# Mako_DSP_Power_R1_1.net
KiCad netlist of a schematic drawn in Altium Designer
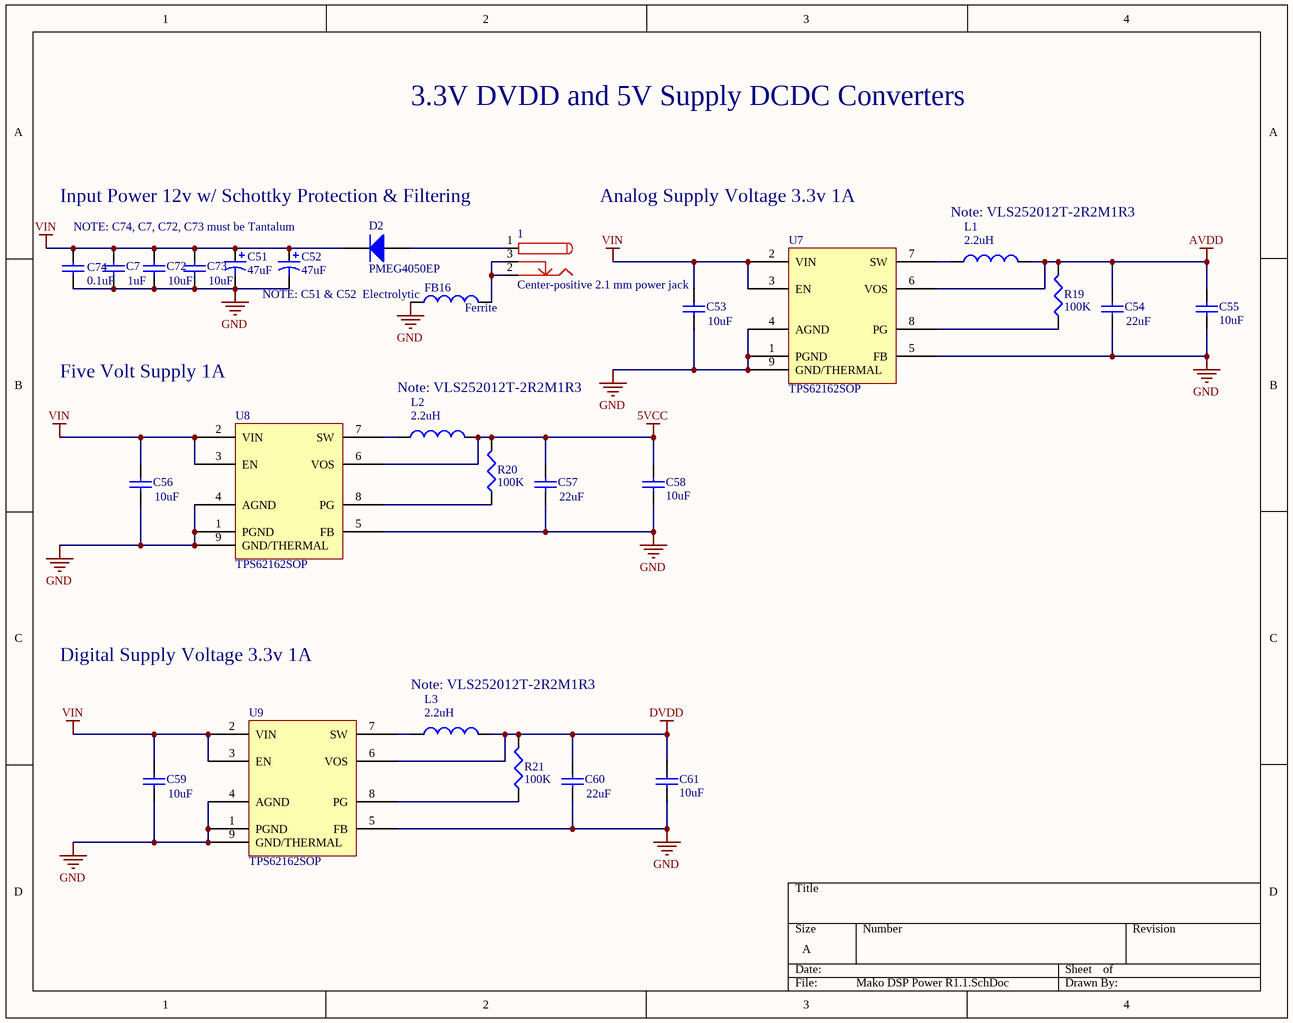
[diagram p0: Mako DSP Power R1.1.SchDoc]

(export (version "E")
  (design (tool "Eeschema 10.0.6"))
  (components
    (comp (ref "1")
      (value "Center-positive 2.1 mm power jack")
      (footprint "PJ-102AH")
      (description "Power jack")
      (fields (field (name "PUBLISHER") "Altium Limited"))
      (libsource (lib "Rascal") (part "PWR2.5"))
    )
    (comp (ref "C7")
      (value "1uF")
      (footprint "C1206")
      (description "Capacitor (Semiconductor SIM Model)")
      (fields (field (name "Comment") "Cap Semi") (field (name "PUBLISHER") "Altium Limited"))
      (libsource (lib "Miscellaneous Devices") (part "Cap Semi"))
    )
    (comp (ref "C51")
      (value "47uF")
      (footprint "CAPPR2.5-6.3x5")
      (description "Polarized Capacitor (Radial)")
      (fields (field (name "Comment") "Cap Pol1") (field (name "PUBLISHER") "Altium Limited"))
      (libsource (lib "Miscellaneous Devices") (part "Cap Pol1"))
    )
    (comp (ref "C52")
      (value "47uF")
      (footprint "CAPPR2.5-6.3x5")
      (description "Polarized Capacitor (Radial)")
      (fields (field (name "Comment") "Cap Pol1") (field (name "PUBLISHER") "Altium Limited"))
      (libsource (lib "Miscellaneous Devices") (part "Cap Pol1"))
    )
    (comp (ref "C53")
      (value "10uF")
      (footprint "C1206")
      (description "Capacitor (Semiconductor SIM Model)")
      (fields (field (name "Comment") "Cap Semi") (field (name "PUBLISHER") "Altium Limited"))
      (libsource (lib "Miscellaneous Devices") (part "Cap Semi"))
    )
    (comp (ref "C54")
      (value "22uF")
      (footprint "C1206")
      (description "Capacitor (Semiconductor SIM Model)")
      (fields (field (name "Comment") "Cap Semi") (field (name "PUBLISHER") "Altium Limited"))
      (libsource (lib "Miscellaneous Devices") (part "Cap Semi"))
    )
    (comp (ref "C55")
      (value "10uF")
      (footprint "Panasonic VS B")
      (description "Capacitor (Semiconductor SIM Model)")
      (fields (field (name "Comment") "Cap Semi") (field (name "PUBLISHER") "Altium Limited"))
      (libsource (lib "Miscellaneous Devices") (part "Cap Semi"))
    )
    (comp (ref "C56")
      (value "10uF")
      (footprint "C1206")
      (description "Capacitor (Semiconductor SIM Model)")
      (fields (field (name "Comment") "Cap Semi") (field (name "PUBLISHER") "Altium Limited"))
      (libsource (lib "Miscellaneous Devices") (part "Cap Semi"))
    )
    (comp (ref "C57")
      (value "22uF")
      (footprint "C1206")
      (description "Capacitor (Semiconductor SIM Model)")
      (fields (field (name "Comment") "Cap Semi") (field (name "PUBLISHER") "Altium Limited"))
      (libsource (lib "Miscellaneous Devices") (part "Cap Semi"))
    )
    (comp (ref "C58")
      (value "10uF")
      (footprint "Panasonic VS B")
      (description "Capacitor (Semiconductor SIM Model)")
      (fields (field (name "Comment") "Cap Semi") (field (name "PUBLISHER") "Altium Limited"))
      (libsource (lib "Miscellaneous Devices") (part "Cap Semi"))
    )
    (comp (ref "C59")
      (value "10uF")
      (footprint "C1206")
      (description "Capacitor (Semiconductor SIM Model)")
      (fields (field (name "Comment") "Cap Semi") (field (name "PUBLISHER") "Altium Limited"))
      (libsource (lib "Miscellaneous Devices") (part "Cap Semi"))
    )
    (comp (ref "C60")
      (value "22uF")
      (footprint "C1206")
      (description "Capacitor (Semiconductor SIM Model)")
      (fields (field (name "Comment") "Cap Semi") (field (name "PUBLISHER") "Altium Limited"))
      (libsource (lib "Miscellaneous Devices") (part "Cap Semi"))
    )
    (comp (ref "C61")
      (value "10uF")
      (footprint "Panasonic VS B")
      (description "Capacitor (Semiconductor SIM Model)")
      (fields (field (name "Comment") "Cap Semi") (field (name "PUBLISHER") "Altium Limited"))
      (libsource (lib "Miscellaneous Devices") (part "Cap Semi"))
    )
    (comp (ref "C72")
      (value "10uF")
      (footprint "C1206")
      (description "Capacitor (Semiconductor SIM Model)")
      (fields (field (name "Comment") "Cap Semi") (field (name "PUBLISHER") "Altium Limited"))
      (libsource (lib "Miscellaneous Devices") (part "Cap Semi"))
    )
    (comp (ref "C73")
      (value "10uF")
      (footprint "C1206")
      (description "Capacitor (Semiconductor SIM Model)")
      (fields (field (name "Comment") "Cap Semi") (field (name "PUBLISHER") "Altium Limited"))
      (libsource (lib "Miscellaneous Devices") (part "Cap Semi"))
    )
    (comp (ref "C74")
      (value "0.1uF")
      (footprint "C1206")
      (description "Capacitor (Semiconductor SIM Model)")
      (fields (field (name "Comment") "Cap Semi") (field (name "PUBLISHER") "Altium Limited"))
      (libsource (lib "Miscellaneous Devices") (part "Cap Semi"))
    )
    (comp (ref "D2")
      (value "PMEG4050EP")
      (footprint "PMEG4050EP")
      (description "Default Diode")
      (fields (field (name "PUBLISHER") "Altium Limited"))
      (libsource (lib "Miscellaneous Devices") (part "Diode"))
    )
    (comp (ref "FB16")
      (value "Ferrite")
      (footprint "SM 0805 - gap trimmed")
      (description "Inductor")
      (fields (field (name "PUBLISHER") "Altium Limited"))
      (libsource (lib "Miscellaneous Devices") (part "Inductor"))
    )
    (comp (ref "L1")
      (value "2.2uH")
      (footprint "VLS252012T-2R2M1R3")
      (description "Inductor")
      (fields (field (name "PUBLISHER") "Altium Limited"))
      (libsource (lib "Miscellaneous Devices") (part "Inductor"))
    )
    (comp (ref "L2")
      (value "2.2uH")
      (footprint "VLS252012T-2R2M1R3")
      (description "Inductor")
      (fields (field (name "PUBLISHER") "Altium Limited"))
      (libsource (lib "Miscellaneous Devices") (part "Inductor"))
    )
    (comp (ref "L3")
      (value "2.2uH")
      (footprint "VLS252012T-2R2M1R3")
      (description "Inductor")
      (fields (field (name "PUBLISHER") "Altium Limited"))
      (libsource (lib "Miscellaneous Devices") (part "Inductor"))
    )
    (comp (ref "R19")
      (value "100K")
      (footprint "RESC2012L")
      (description "Resistor")
      (fields (field (name "Comment") "Res3") (field (name "PUBLISHER") "Altium Limited"))
      (libsource (lib "Miscellaneous Devices") (part "Res3"))
    )
    (comp (ref "R20")
      (value "100K")
      (footprint "RESC2012L")
      (description "Resistor")
      (fields (field (name "Comment") "Res3") (field (name "PUBLISHER") "Altium Limited"))
      (libsource (lib "Miscellaneous Devices") (part "Res3"))
    )
    (comp (ref "R21")
      (value "100K")
      (footprint "RESC2012L")
      (description "Resistor")
      (fields (field (name "Comment") "Res3") (field (name "PUBLISHER") "Altium Limited"))
      (libsource (lib "Miscellaneous Devices") (part "Res3"))
    )
    (comp (ref "U7")
      (value "TPS62162SOP")
      (footprint "TPS62162SOP")
      (libsource (lib "Adams Altium Library") (part "TPS62162SOP"))
    )
    (comp (ref "U8")
      (value "TPS62162SOP")
      (footprint "TPS62162SOP")
      (libsource (lib "Adams Altium Library") (part "TPS62162SOP"))
    )
    (comp (ref "U9")
      (value "TPS62162SOP")
      (footprint "TPS62162SOP")
      (libsource (lib "Adams Altium Library") (part "TPS62162SOP"))
    )
  )
  (nets
    (net (code "1") (name "5VCC") (class "Default")
      (node (ref "C57") (pin "2") (pinfunction "2_2") (pintype "passive"))
      (node (ref "C58") (pin "1") (pinfunction "1_1") (pintype "passive"))
      (node (ref "L2") (pin "2") (pinfunction "2_2") (pintype "passive"))
      (node (ref "R20") (pin "2") (pinfunction "2_2") (pintype "passive"))
      (node (ref "U8") (pin "6") (pinfunction "VOS_6") (pintype "passive"))
    )
    (net (code "2") (name "AVDD") (class "Default")
      (node (ref "C54") (pin "2") (pinfunction "2_2") (pintype "passive"))
      (node (ref "C55") (pin "1") (pinfunction "1_1") (pintype "passive"))
      (node (ref "L1") (pin "2") (pinfunction "2_2") (pintype "passive"))
      (node (ref "R19") (pin "2") (pinfunction "2_2") (pintype "passive"))
      (node (ref "U7") (pin "6") (pinfunction "VOS_6") (pintype "passive"))
    )
    (net (code "3") (name "DVDD") (class "Default")
      (node (ref "C60") (pin "2") (pinfunction "2_2") (pintype "passive"))
      (node (ref "C61") (pin "1") (pinfunction "1_1") (pintype "passive"))
      (node (ref "L3") (pin "2") (pinfunction "2_2") (pintype "passive"))
      (node (ref "R21") (pin "2") (pinfunction "2_2") (pintype "passive"))
      (node (ref "U9") (pin "6") (pinfunction "VOS_6") (pintype "passive"))
    )
    (net (code "4") (name "GND") (class "Default")
      (node (ref "C51") (pin "2") (pinfunction "2_2") (pintype "passive"))
      (node (ref "C52") (pin "2") (pinfunction "2_2") (pintype "passive"))
      (node (ref "C53") (pin "1") (pinfunction "1_1") (pintype "passive"))
      (node (ref "C54") (pin "1") (pinfunction "1_1") (pintype "passive"))
      (node (ref "C55") (pin "2") (pinfunction "2_2") (pintype "passive"))
      (node (ref "C56") (pin "1") (pinfunction "1_1") (pintype "passive"))
      (node (ref "C57") (pin "1") (pinfunction "1_1") (pintype "passive"))
      (node (ref "C58") (pin "2") (pinfunction "2_2") (pintype "passive"))
      (node (ref "C59") (pin "1") (pinfunction "1_1") (pintype "passive"))
      (node (ref "C60") (pin "1") (pinfunction "1_1") (pintype "passive"))
      (node (ref "C61") (pin "2") (pinfunction "2_2") (pintype "passive"))
      (node (ref "C7") (pin "1") (pinfunction "1_1") (pintype "passive"))
      (node (ref "C72") (pin "1") (pinfunction "1_1") (pintype "passive"))
      (node (ref "C73") (pin "1") (pinfunction "1_1") (pintype "passive"))
      (node (ref "C74") (pin "1") (pinfunction "1_1") (pintype "passive"))
      (node (ref "FB16") (pin "1") (pinfunction "1_1") (pintype "passive"))
      (node (ref "U7") (pin "1") (pinfunction "PGND_1") (pintype "passive"))
      (node (ref "U7") (pin "4") (pinfunction "AGND_4") (pintype "passive"))
      (node (ref "U7") (pin "5") (pinfunction "FB_5") (pintype "passive"))
      (node (ref "U7") (pin "9") (pinfunction "GND/THERMAL_9") (pintype "passive"))
      (node (ref "U8") (pin "1") (pinfunction "PGND_1") (pintype "passive"))
      (node (ref "U8") (pin "4") (pinfunction "AGND_4") (pintype "passive"))
      (node (ref "U8") (pin "5") (pinfunction "FB_5") (pintype "passive"))
      (node (ref "U8") (pin "9") (pinfunction "GND/THERMAL_9") (pintype "passive"))
      (node (ref "U9") (pin "1") (pinfunction "PGND_1") (pintype "passive"))
      (node (ref "U9") (pin "4") (pinfunction "AGND_4") (pintype "passive"))
      (node (ref "U9") (pin "5") (pinfunction "FB_5") (pintype "passive"))
      (node (ref "U9") (pin "9") (pinfunction "GND/THERMAL_9") (pintype "passive"))
    )
    (net (code "5") (name "Net-(1-Pad2)") (class "Default")
      (node (ref "1") (pin "2") (pinfunction "2_2") (pintype "power_in"))
      (node (ref "1") (pin "3") (pinfunction "3_3") (pintype "power_in"))
      (node (ref "FB16") (pin "2") (pinfunction "2_2") (pintype "passive"))
    )
    (net (code "6") (name "Net-(D2-K)") (class "Default")
      (node (ref "1") (pin "1") (pinfunction "1_1") (pintype "power_in"))
      (node (ref "D2") (pin "2") (pinfunction "K_2") (pintype "passive"))
    )
    (net (code "7") (name "Net-(U7-PG)") (class "Default")
      (node (ref "R19") (pin "1") (pinfunction "1_1") (pintype "passive"))
      (node (ref "U7") (pin "8") (pinfunction "PG_8") (pintype "passive"))
    )
    (net (code "8") (name "Net-(U7-SW)") (class "Default")
      (node (ref "L1") (pin "1") (pinfunction "1_1") (pintype "passive"))
      (node (ref "U7") (pin "7") (pinfunction "SW_7") (pintype "passive"))
    )
    (net (code "9") (name "Net-(U8-PG)") (class "Default")
      (node (ref "R20") (pin "1") (pinfunction "1_1") (pintype "passive"))
      (node (ref "U8") (pin "8") (pinfunction "PG_8") (pintype "passive"))
    )
    (net (code "10") (name "Net-(U8-SW)") (class "Default")
      (node (ref "L2") (pin "1") (pinfunction "1_1") (pintype "passive"))
      (node (ref "U8") (pin "7") (pinfunction "SW_7") (pintype "passive"))
    )
    (net (code "11") (name "Net-(U9-PG)") (class "Default")
      (node (ref "R21") (pin "1") (pinfunction "1_1") (pintype "passive"))
      (node (ref "U9") (pin "8") (pinfunction "PG_8") (pintype "passive"))
    )
    (net (code "12") (name "Net-(U9-SW)") (class "Default")
      (node (ref "L3") (pin "1") (pinfunction "1_1") (pintype "passive"))
      (node (ref "U9") (pin "7") (pinfunction "SW_7") (pintype "passive"))
    )
    (net (code "13") (name "VIN") (class "Default")
      (node (ref "C51") (pin "1") (pinfunction "1_1") (pintype "passive"))
      (node (ref "C52") (pin "1") (pinfunction "1_1") (pintype "passive"))
      (node (ref "C53") (pin "2") (pinfunction "2_2") (pintype "passive"))
      (node (ref "C56") (pin "2") (pinfunction "2_2") (pintype "passive"))
      (node (ref "C59") (pin "2") (pinfunction "2_2") (pintype "passive"))
      (node (ref "C7") (pin "2") (pinfunction "2_2") (pintype "passive"))
      (node (ref "C72") (pin "2") (pinfunction "2_2") (pintype "passive"))
      (node (ref "C73") (pin "2") (pinfunction "2_2") (pintype "passive"))
      (node (ref "C74") (pin "2") (pinfunction "2_2") (pintype "passive"))
      (node (ref "D2") (pin "1") (pinfunction "A_1") (pintype "passive"))
      (node (ref "U7") (pin "2") (pinfunction "VIN_2") (pintype "passive"))
      (node (ref "U7") (pin "3") (pinfunction "EN_3") (pintype "passive"))
      (node (ref "U8") (pin "2") (pinfunction "VIN_2") (pintype "passive"))
      (node (ref "U8") (pin "3") (pinfunction "EN_3") (pintype "passive"))
      (node (ref "U9") (pin "2") (pinfunction "VIN_2") (pintype "passive"))
      (node (ref "U9") (pin "3") (pinfunction "EN_3") (pintype "passive"))
    )
  )
)
